# VHDL_projekt.net
KiCad netlist of a schematic drawn in EAGLE
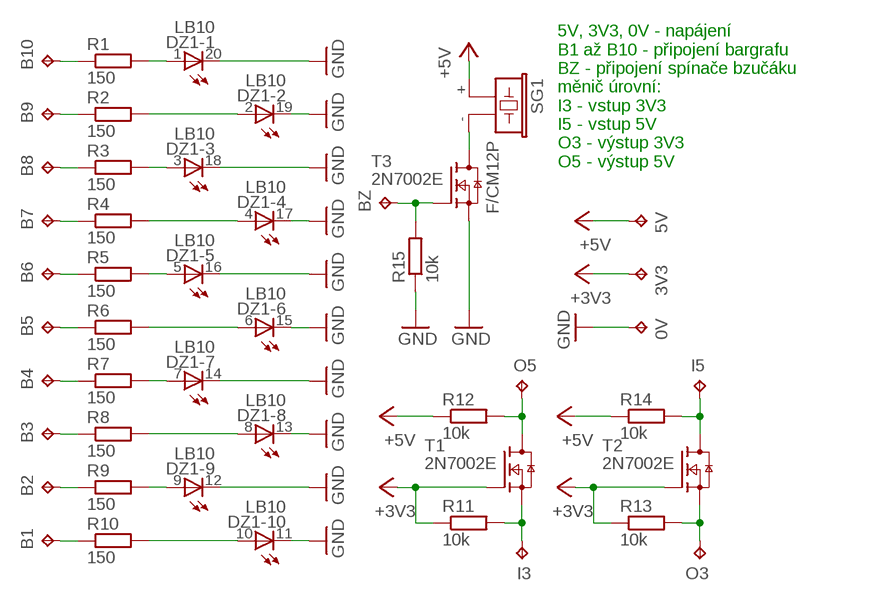
[diagram p0: schematic, sheet 1]

(export (version "E")
  (design (tool "Eeschema 10.0.6"))
  (components
    (comp (ref "0V")
      (value "TPPAD1-13Y")
      (footprint "eagle-import:P1-13Y")
      (libsource (lib "eagle-import") (part "TPPAD1-13Y"))
    )
    (comp (ref "3V3")
      (value "TPPAD1-13Y")
      (footprint "eagle-import:P1-13Y")
      (libsource (lib "eagle-import") (part "TPPAD1-13Y"))
    )
    (comp (ref "5V")
      (value "TPPAD1-13Y")
      (footprint "eagle-import:P1-13Y")
      (libsource (lib "eagle-import") (part "TPPAD1-13Y"))
    )
    (comp (ref "B1")
      (value "TPPAD1-13Y")
      (footprint "eagle-import:P1-13Y")
      (libsource (lib "eagle-import") (part "TPPAD1-13Y"))
    )
    (comp (ref "B2")
      (value "TPPAD1-13Y")
      (footprint "eagle-import:P1-13Y")
      (libsource (lib "eagle-import") (part "TPPAD1-13Y"))
    )
    (comp (ref "B3")
      (value "TPPAD1-13Y")
      (footprint "eagle-import:P1-13Y")
      (libsource (lib "eagle-import") (part "TPPAD1-13Y"))
    )
    (comp (ref "B4")
      (value "TPPAD1-13Y")
      (footprint "eagle-import:P1-13Y")
      (libsource (lib "eagle-import") (part "TPPAD1-13Y"))
    )
    (comp (ref "B5")
      (value "TPPAD1-13Y")
      (footprint "eagle-import:P1-13Y")
      (libsource (lib "eagle-import") (part "TPPAD1-13Y"))
    )
    (comp (ref "B6")
      (value "TPPAD1-13Y")
      (footprint "eagle-import:P1-13Y")
      (libsource (lib "eagle-import") (part "TPPAD1-13Y"))
    )
    (comp (ref "B7")
      (value "TPPAD1-13Y")
      (footprint "eagle-import:P1-13Y")
      (libsource (lib "eagle-import") (part "TPPAD1-13Y"))
    )
    (comp (ref "B8")
      (value "TPPAD1-13Y")
      (footprint "eagle-import:P1-13Y")
      (libsource (lib "eagle-import") (part "TPPAD1-13Y"))
    )
    (comp (ref "B9")
      (value "TPPAD1-13Y")
      (footprint "eagle-import:P1-13Y")
      (libsource (lib "eagle-import") (part "TPPAD1-13Y"))
    )
    (comp (ref "B10")
      (value "TPPAD1-13Y")
      (footprint "eagle-import:P1-13Y")
      (libsource (lib "eagle-import") (part "TPPAD1-13Y"))
    )
    (comp (ref "BZ")
      (value "TPPAD1-13Y")
      (footprint "eagle-import:P1-13Y")
      (libsource (lib "eagle-import") (part "TPPAD1-13Y"))
    )
    (comp (ref "DZ1")
      (value "LB10")
      (footprint "eagle-import:LB10")
      (libsource (lib "eagle-import") (part "LB10"))
    )
    (comp (ref "I3")
      (value "TPPAD1-13Y")
      (footprint "eagle-import:P1-13Y")
      (libsource (lib "eagle-import") (part "TPPAD1-13Y"))
    )
    (comp (ref "I5")
      (value "TPPAD1-13Y")
      (footprint "eagle-import:P1-13Y")
      (libsource (lib "eagle-import") (part "TPPAD1-13Y"))
    )
    (comp (ref "O3")
      (value "TPPAD1-13Y")
      (footprint "eagle-import:P1-13Y")
      (libsource (lib "eagle-import") (part "TPPAD1-13Y"))
    )
    (comp (ref "O5")
      (value "TPPAD1-13Y")
      (footprint "eagle-import:P1-13Y")
      (libsource (lib "eagle-import") (part "TPPAD1-13Y"))
    )
    (comp (ref "R1")
      (value "150")
      (footprint "eagle-import:R1206")
      (libsource (lib "eagle-import") (part "R-EU_R1206"))
    )
    (comp (ref "R2")
      (value "150")
      (footprint "eagle-import:R1206")
      (libsource (lib "eagle-import") (part "R-EU_R1206"))
    )
    (comp (ref "R3")
      (value "150")
      (footprint "eagle-import:R1206")
      (libsource (lib "eagle-import") (part "R-EU_R1206"))
    )
    (comp (ref "R4")
      (value "150")
      (footprint "eagle-import:R1206")
      (libsource (lib "eagle-import") (part "R-EU_R1206"))
    )
    (comp (ref "R5")
      (value "150")
      (footprint "eagle-import:R1206")
      (libsource (lib "eagle-import") (part "R-EU_R1206"))
    )
    (comp (ref "R6")
      (value "150")
      (footprint "eagle-import:R1206")
      (libsource (lib "eagle-import") (part "R-EU_R1206"))
    )
    (comp (ref "R7")
      (value "150")
      (footprint "eagle-import:R1206")
      (libsource (lib "eagle-import") (part "R-EU_R1206"))
    )
    (comp (ref "R8")
      (value "150")
      (footprint "eagle-import:R1206")
      (libsource (lib "eagle-import") (part "R-EU_R1206"))
    )
    (comp (ref "R9")
      (value "150")
      (footprint "eagle-import:R1206")
      (libsource (lib "eagle-import") (part "R-EU_R1206"))
    )
    (comp (ref "R10")
      (value "150")
      (footprint "eagle-import:R1206")
      (libsource (lib "eagle-import") (part "R-EU_R1206"))
    )
    (comp (ref "R11")
      (value "10k")
      (footprint "eagle-import:R1206")
      (libsource (lib "eagle-import") (part "R-EU_R1206"))
    )
    (comp (ref "R12")
      (value "10k")
      (footprint "eagle-import:R1206")
      (libsource (lib "eagle-import") (part "R-EU_R1206"))
    )
    (comp (ref "R13")
      (value "10k")
      (footprint "eagle-import:R1206")
      (libsource (lib "eagle-import") (part "R-EU_R1206"))
    )
    (comp (ref "R14")
      (value "10k")
      (footprint "eagle-import:R1206")
      (libsource (lib "eagle-import") (part "R-EU_R1206"))
    )
    (comp (ref "R15")
      (value "10k")
      (footprint "eagle-import:R1206")
      (libsource (lib "eagle-import") (part "R-EU_R1206"))
    )
    (comp (ref "SG1")
      (value "F/CM12P")
      (footprint "eagle-import:F_CM12P")
      (libsource (lib "eagle-import") (part "F/CM12P"))
    )
    (comp (ref "T1")
      (value "2N7002E")
      (footprint "eagle-import:SOT23")
      (libsource (lib "eagle-import") (part "2N7002E"))
    )
    (comp (ref "T2")
      (value "2N7002E")
      (footprint "eagle-import:SOT23")
      (libsource (lib "eagle-import") (part "2N7002E"))
    )
    (comp (ref "T3")
      (value "2N7002E")
      (footprint "eagle-import:SOT23")
      (libsource (lib "eagle-import") (part "2N7002E"))
    )
  )
  (nets
    (net (code "1") (name "+3V3") (class "Default")
      (node (ref "3V3") (pin "TP") (pinfunction "TP_TP") (pintype "input"))
      (node (ref "R11") (pin "1") (pinfunction "1_1") (pintype "passive"))
      (node (ref "R13") (pin "1") (pinfunction "1_1") (pintype "passive"))
      (node (ref "T1") (pin "1") (pinfunction "G_1") (pintype "passive"))
      (node (ref "T2") (pin "1") (pinfunction "G_1") (pintype "passive"))
    )
    (net (code "2") (name "+5V") (class "Default")
      (node (ref "5V") (pin "TP") (pinfunction "TP_TP") (pintype "input"))
      (node (ref "R12") (pin "1") (pinfunction "1_1") (pintype "passive"))
      (node (ref "R14") (pin "1") (pinfunction "1_1") (pintype "passive"))
      (node (ref "SG1") (pin "+") (pinfunction "1_+") (pintype "passive"))
    )
    (net (code "3") (name "GND") (class "Default")
      (node (ref "0V") (pin "TP") (pinfunction "TP_TP") (pintype "input"))
      (node (ref "DZ1") (pin "11") (pinfunction "C_11") (pintype "passive"))
      (node (ref "DZ1") (pin "12") (pinfunction "C_12") (pintype "passive"))
      (node (ref "DZ1") (pin "13") (pinfunction "C_13") (pintype "passive"))
      (node (ref "DZ1") (pin "14") (pinfunction "C_14") (pintype "passive"))
      (node (ref "DZ1") (pin "15") (pinfunction "C_15") (pintype "passive"))
      (node (ref "DZ1") (pin "16") (pinfunction "C_16") (pintype "passive"))
      (node (ref "DZ1") (pin "17") (pinfunction "C_17") (pintype "passive"))
      (node (ref "DZ1") (pin "18") (pinfunction "C_18") (pintype "passive"))
      (node (ref "DZ1") (pin "19") (pinfunction "C_19") (pintype "passive"))
      (node (ref "DZ1") (pin "20") (pinfunction "C_20") (pintype "passive"))
      (node (ref "R15") (pin "1") (pinfunction "1_1") (pintype "passive"))
      (node (ref "T3") (pin "2") (pinfunction "S_2") (pintype "passive"))
    )
    (net (code "4") (name "Net-(B1-PadTP)") (class "Default")
      (node (ref "B1") (pin "TP") (pinfunction "TP_TP") (pintype "input"))
      (node (ref "R10") (pin "1") (pinfunction "1_1") (pintype "passive"))
    )
    (net (code "5") (name "Net-(B2-PadTP)") (class "Default")
      (node (ref "B2") (pin "TP") (pinfunction "TP_TP") (pintype "input"))
      (node (ref "R9") (pin "1") (pinfunction "1_1") (pintype "passive"))
    )
    (net (code "6") (name "Net-(B3-PadTP)") (class "Default")
      (node (ref "B3") (pin "TP") (pinfunction "TP_TP") (pintype "input"))
      (node (ref "R8") (pin "1") (pinfunction "1_1") (pintype "passive"))
    )
    (net (code "7") (name "Net-(B4-PadTP)") (class "Default")
      (node (ref "B4") (pin "TP") (pinfunction "TP_TP") (pintype "input"))
      (node (ref "R7") (pin "1") (pinfunction "1_1") (pintype "passive"))
    )
    (net (code "8") (name "Net-(B5-PadTP)") (class "Default")
      (node (ref "B5") (pin "TP") (pinfunction "TP_TP") (pintype "input"))
      (node (ref "R6") (pin "1") (pinfunction "1_1") (pintype "passive"))
    )
    (net (code "9") (name "Net-(B6-PadTP)") (class "Default")
      (node (ref "B6") (pin "TP") (pinfunction "TP_TP") (pintype "input"))
      (node (ref "R5") (pin "1") (pinfunction "1_1") (pintype "passive"))
    )
    (net (code "10") (name "Net-(B7-PadTP)") (class "Default")
      (node (ref "B7") (pin "TP") (pinfunction "TP_TP") (pintype "input"))
      (node (ref "R4") (pin "1") (pinfunction "1_1") (pintype "passive"))
    )
    (net (code "11") (name "Net-(B8-PadTP)") (class "Default")
      (node (ref "B8") (pin "TP") (pinfunction "TP_TP") (pintype "input"))
      (node (ref "R3") (pin "1") (pinfunction "1_1") (pintype "passive"))
    )
    (net (code "12") (name "Net-(B9-PadTP)") (class "Default")
      (node (ref "B9") (pin "TP") (pinfunction "TP_TP") (pintype "input"))
      (node (ref "R2") (pin "1") (pinfunction "1_1") (pintype "passive"))
    )
    (net (code "13") (name "Net-(B10-PadTP)") (class "Default")
      (node (ref "B10") (pin "TP") (pinfunction "TP_TP") (pintype "input"))
      (node (ref "R1") (pin "1") (pinfunction "1_1") (pintype "passive"))
    )
    (net (code "14") (name "Net-(DZ1A-A)") (class "Default")
      (node (ref "DZ1") (pin "1") (pinfunction "A_1") (pintype "passive"))
      (node (ref "R1") (pin "2") (pinfunction "2_2") (pintype "passive"))
    )
    (net (code "15") (name "Net-(DZ1B-A)") (class "Default")
      (node (ref "DZ1") (pin "10") (pinfunction "A_10") (pintype "passive"))
      (node (ref "R10") (pin "2") (pinfunction "2_2") (pintype "passive"))
    )
    (net (code "16") (name "Net-(DZ1C-A)") (class "Default")
      (node (ref "DZ1") (pin "2") (pinfunction "A_2") (pintype "passive"))
      (node (ref "R2") (pin "2") (pinfunction "2_2") (pintype "passive"))
    )
    (net (code "17") (name "Net-(DZ1D-A)") (class "Default")
      (node (ref "DZ1") (pin "3") (pinfunction "A_3") (pintype "passive"))
      (node (ref "R3") (pin "2") (pinfunction "2_2") (pintype "passive"))
    )
    (net (code "18") (name "Net-(DZ1E-A)") (class "Default")
      (node (ref "DZ1") (pin "4") (pinfunction "A_4") (pintype "passive"))
      (node (ref "R4") (pin "2") (pinfunction "2_2") (pintype "passive"))
    )
    (net (code "19") (name "Net-(DZ1F-A)") (class "Default")
      (node (ref "DZ1") (pin "5") (pinfunction "A_5") (pintype "passive"))
      (node (ref "R5") (pin "2") (pinfunction "2_2") (pintype "passive"))
    )
    (net (code "20") (name "Net-(DZ1G-A)") (class "Default")
      (node (ref "DZ1") (pin "6") (pinfunction "A_6") (pintype "passive"))
      (node (ref "R6") (pin "2") (pinfunction "2_2") (pintype "passive"))
    )
    (net (code "21") (name "Net-(DZ1H-A)") (class "Default")
      (node (ref "DZ1") (pin "7") (pinfunction "A_7") (pintype "passive"))
      (node (ref "R7") (pin "2") (pinfunction "2_2") (pintype "passive"))
    )
    (net (code "22") (name "Net-(DZ1I-A)") (class "Default")
      (node (ref "DZ1") (pin "8") (pinfunction "A_8") (pintype "passive"))
      (node (ref "R8") (pin "2") (pinfunction "2_2") (pintype "passive"))
    )
    (net (code "23") (name "Net-(DZ1J-A)") (class "Default")
      (node (ref "DZ1") (pin "9") (pinfunction "A_9") (pintype "passive"))
      (node (ref "R9") (pin "2") (pinfunction "2_2") (pintype "passive"))
    )
    (net (code "24") (name "Net-(SG1-2)") (class "Default")
      (node (ref "SG1") (pin "-") (pinfunction "2_-") (pintype "passive"))
      (node (ref "T3") (pin "3") (pinfunction "D_3") (pintype "passive"))
    )
    (net (code "25") (name "Net-(T1-D)") (class "Default")
      (node (ref "O5") (pin "TP") (pinfunction "TP_TP") (pintype "input"))
      (node (ref "R12") (pin "2") (pinfunction "2_2") (pintype "passive"))
      (node (ref "T1") (pin "3") (pinfunction "D_3") (pintype "passive"))
    )
    (net (code "26") (name "Net-(T1-S)") (class "Default")
      (node (ref "I3") (pin "TP") (pinfunction "TP_TP") (pintype "input"))
      (node (ref "R11") (pin "2") (pinfunction "2_2") (pintype "passive"))
      (node (ref "T1") (pin "2") (pinfunction "S_2") (pintype "passive"))
    )
    (net (code "27") (name "Net-(T2-D)") (class "Default")
      (node (ref "I5") (pin "TP") (pinfunction "TP_TP") (pintype "input"))
      (node (ref "R14") (pin "2") (pinfunction "2_2") (pintype "passive"))
      (node (ref "T2") (pin "3") (pinfunction "D_3") (pintype "passive"))
    )
    (net (code "28") (name "Net-(T2-S)") (class "Default")
      (node (ref "O3") (pin "TP") (pinfunction "TP_TP") (pintype "input"))
      (node (ref "R13") (pin "2") (pinfunction "2_2") (pintype "passive"))
      (node (ref "T2") (pin "2") (pinfunction "S_2") (pintype "passive"))
    )
    (net (code "29") (name "Net-(T3-G)") (class "Default")
      (node (ref "BZ") (pin "TP") (pinfunction "TP_TP") (pintype "input"))
      (node (ref "R15") (pin "2") (pinfunction "2_2") (pintype "passive"))
      (node (ref "T3") (pin "1") (pinfunction "G_1") (pintype "passive"))
    )
  )
)
